# moxon_915_passives.net
KiCad netlist of a schematic drawn in EAGLE
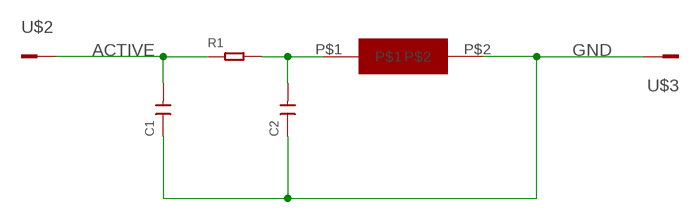
[diagram p0: schematic, sheet 1]

(export (version "E")
  (design (tool "Eeschema 10.0.6"))
  (components
    (comp (ref "C1")
      (value "1uf")
      (footprint "eagle-import:C0805")
      (fields (field (name "MPN") "CC0805KKX7R8BB105"))
      (libsource (lib "eagle-import") (part "CERAMIC-1UF-25V-10%-X7R(0805)"))
    )
    (comp (ref "C2")
      (value "1uf")
      (footprint "eagle-import:C0805")
      (fields (field (name "MPN") "CC0805KKX7R8BB105"))
      (libsource (lib "eagle-import") (part "CERAMIC-1UF-25V-10%-X7R(0805)"))
    )
    (comp (ref "R1")
      (value "1K")
      (footprint "eagle-import:R0805")
      (fields (field (name "MPN") "RC0805JR-071KL"))
      (libsource (lib "eagle-import") (part "SMD-RES-2.2K-1%-1/8W(0805)"))
    )
    (comp (ref "U$1")
      (value "MOXON-915MOX1")
      (footprint "eagle-import:MOXON-915")
      (libsource (lib "eagle-import") (part "MOXON-915MOX1"))
    )
    (comp (ref "U$2")
      (value "CONN-1PAD2")
      (footprint "eagle-import:PAD2")
      (libsource (lib "eagle-import") (part "CONN-1PAD2"))
    )
    (comp (ref "U$3")
      (value "CONN-1PAD2")
      (footprint "eagle-import:PAD2")
      (libsource (lib "eagle-import") (part "CONN-1PAD2"))
    )
  )
  (nets
    (net (code "1") (name "/ACTIVE") (class "Default")
      (node (ref "C1") (pin "2") (pinfunction "2_2") (pintype "passive"))
      (node (ref "R1") (pin "1") (pinfunction "1_1") (pintype "passive"))
      (node (ref "U$2") (pin "P$1") (pinfunction "1_P$1") (pintype "passive"))
    )
    (net (code "2") (name "/GND") (class "Default")
      (node (ref "C1") (pin "1") (pinfunction "1_1") (pintype "passive"))
      (node (ref "C2") (pin "1") (pinfunction "1_1") (pintype "passive"))
      (node (ref "U$1") (pin "P$2") (pinfunction "P$2_P$2") (pintype "bidirectional"))
      (node (ref "U$3") (pin "P$1") (pinfunction "1_P$1") (pintype "passive"))
    )
    (net (code "3") (name "Net-(C2-Pad2)") (class "Default")
      (node (ref "C2") (pin "2") (pinfunction "2_2") (pintype "passive"))
      (node (ref "R1") (pin "2") (pinfunction "2_2") (pintype "passive"))
      (node (ref "U$1") (pin "P$1") (pinfunction "P$1_P$1") (pintype "bidirectional"))
    )
  )
)
